# ESP32_breakout_v3.net
KiCad netlist of a schematic drawn in EAGLE
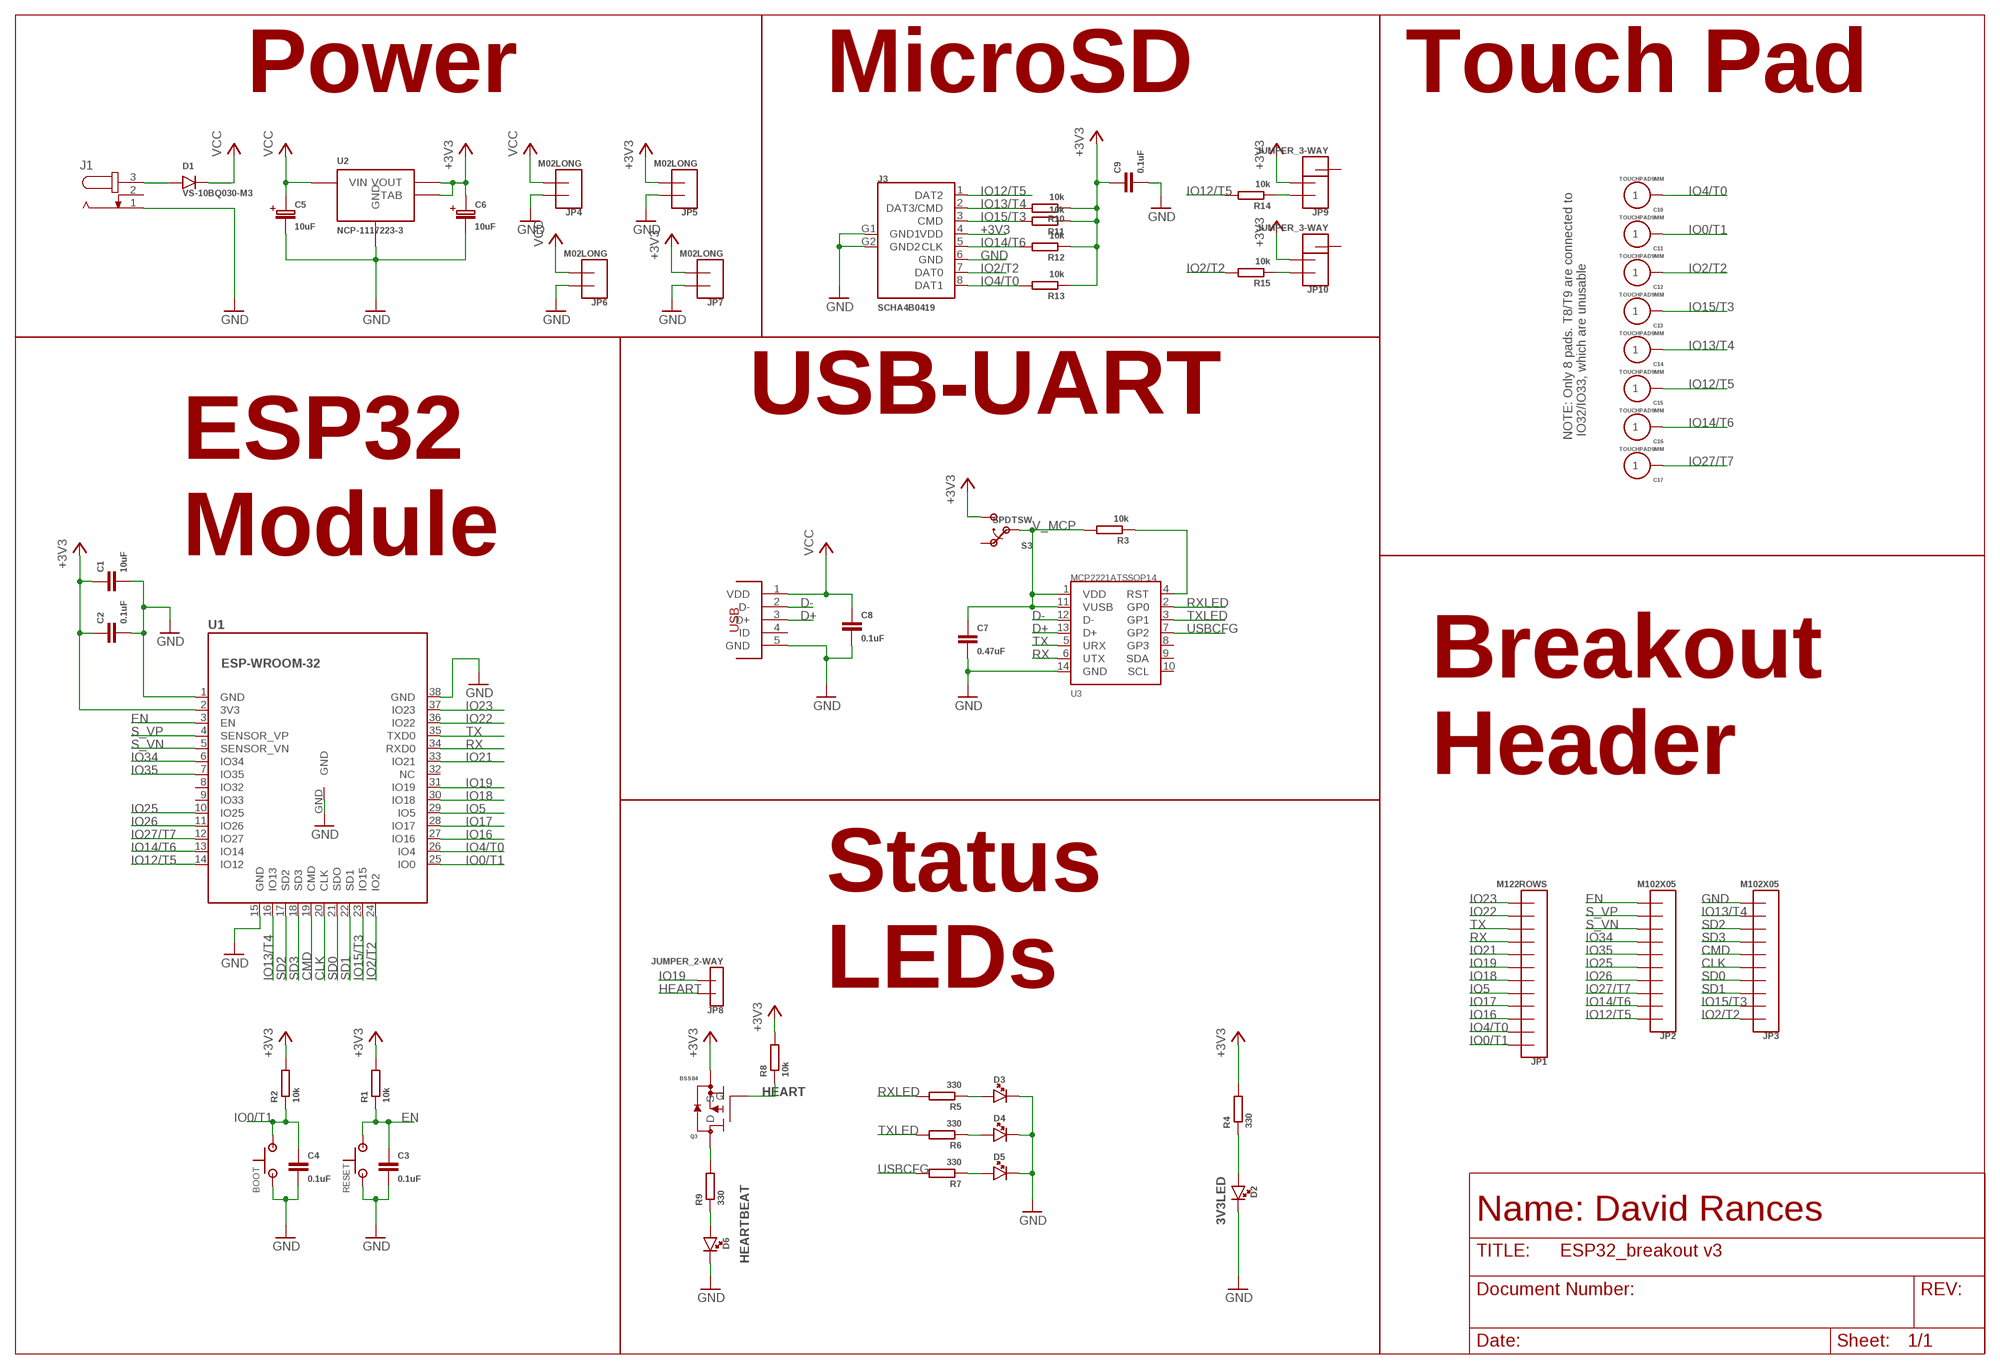
[diagram p0: schematic, sheet 1]

(export (version "E")
  (design (tool "Eeschema 10.0.6"))
  (components
    (comp (ref "BOOT")
      (value "PUSHBUTTONSKHMQME010")
      (footprint "eagle-import:SKHMQME010")
      (libsource (lib "eagle-import") (part "PUSHBUTTONSKHMQME010"))
    )
    (comp (ref "C1")
      (value "10uF")
      (footprint "eagle-import:CAP-0603")
      (libsource (lib "eagle-import") (part "CAP0603"))
    )
    (comp (ref "C2")
      (value "0.1uF")
      (footprint "eagle-import:CAP-0603")
      (libsource (lib "eagle-import") (part "CAP0603"))
    )
    (comp (ref "C3")
      (value "0.1uF")
      (footprint "eagle-import:CAP-0603")
      (libsource (lib "eagle-import") (part "CAP0603"))
    )
    (comp (ref "C4")
      (value "0.1uF")
      (footprint "eagle-import:CAP-0603")
      (libsource (lib "eagle-import") (part "CAP0603"))
    )
    (comp (ref "C5")
      (value "10uF")
      (footprint "eagle-import:B-3528")
      (libsource (lib "eagle-import") (part "CAP-POLARCASEB-3528"))
    )
    (comp (ref "C6")
      (value "10uF")
      (footprint "eagle-import:B-3528")
      (libsource (lib "eagle-import") (part "CAP-POLARCASEB-3528"))
    )
    (comp (ref "C7")
      (value "0.47uF")
      (footprint "eagle-import:CAP-0603")
      (libsource (lib "eagle-import") (part "CAP0603"))
    )
    (comp (ref "C8")
      (value "0.1uF")
      (footprint "eagle-import:CAP-0603")
      (libsource (lib "eagle-import") (part "CAP0603"))
    )
    (comp (ref "C9")
      (value "0.1uF")
      (footprint "eagle-import:CAP-0603")
      (libsource (lib "eagle-import") (part "CAP0603"))
    )
    (comp (ref "C10")
      (value "TOUCHPAD9MM")
      (footprint "eagle-import:TOUCH-9MMX9MM")
      (libsource (lib "eagle-import") (part "TOUCHPAD9MM"))
    )
    (comp (ref "C11")
      (value "TOUCHPAD9MM")
      (footprint "eagle-import:TOUCH-9MMX9MM")
      (libsource (lib "eagle-import") (part "TOUCHPAD9MM"))
    )
    (comp (ref "C12")
      (value "TOUCHPAD9MM")
      (footprint "eagle-import:TOUCH-9MMX9MM")
      (libsource (lib "eagle-import") (part "TOUCHPAD9MM"))
    )
    (comp (ref "C13")
      (value "TOUCHPAD9MM")
      (footprint "eagle-import:TOUCH-9MMX9MM")
      (libsource (lib "eagle-import") (part "TOUCHPAD9MM"))
    )
    (comp (ref "C14")
      (value "TOUCHPAD9MM")
      (footprint "eagle-import:TOUCH-9MMX9MM")
      (libsource (lib "eagle-import") (part "TOUCHPAD9MM"))
    )
    (comp (ref "C15")
      (value "TOUCHPAD9MM")
      (footprint "eagle-import:TOUCH-9MMX9MM")
      (libsource (lib "eagle-import") (part "TOUCHPAD9MM"))
    )
    (comp (ref "C16")
      (value "TOUCHPAD9MM")
      (footprint "eagle-import:TOUCH-9MMX9MM")
      (libsource (lib "eagle-import") (part "TOUCHPAD9MM"))
    )
    (comp (ref "C17")
      (value "TOUCHPAD9MM")
      (footprint "eagle-import:TOUCH-9MMX9MM")
      (libsource (lib "eagle-import") (part "TOUCHPAD9MM"))
    )
    (comp (ref "D1")
      (value "VS-10BQ030-M3")
      (footprint "eagle-import:DO-214AA")
      (libsource (lib "eagle-import") (part "VS-10BQ030-M3"))
    )
    (comp (ref "D2")
      (value "LED1206")
      (footprint "eagle-import:LED-1206")
      (libsource (lib "eagle-import") (part "LED1206"))
    )
    (comp (ref "D3")
      (value "LED1206")
      (footprint "eagle-import:LED-1206")
      (libsource (lib "eagle-import") (part "LED1206"))
    )
    (comp (ref "D4")
      (value "LED1206")
      (footprint "eagle-import:LED-1206")
      (libsource (lib "eagle-import") (part "LED1206"))
    )
    (comp (ref "D5")
      (value "LED1206")
      (footprint "eagle-import:LED-1206")
      (libsource (lib "eagle-import") (part "LED1206"))
    )
    (comp (ref "D6")
      (value "LED1206")
      (footprint "eagle-import:LED-1206")
      (libsource (lib "eagle-import") (part "LED1206"))
    )
    (comp (ref "J1")
      (value "JACK-PLUG0")
      (footprint "eagle-import:SPC4077")
      (libsource (lib "eagle-import") (part "JACK-PLUG0"))
    )
    (comp (ref "J3")
      (value "SCHA4B0419")
      (footprint "eagle-import:MICROSD_SCHA4B0419")
      (libsource (lib "eagle-import") (part "SCHA4B0419"))
    )
    (comp (ref "JP1")
      (value "M122ROWS")
      (footprint "eagle-import:2X06")
      (libsource (lib "eagle-import") (part "M122ROWS"))
    )
    (comp (ref "JP2")
      (value "M102X05")
      (footprint "eagle-import:2X05")
      (libsource (lib "eagle-import") (part "M102X05"))
    )
    (comp (ref "JP3")
      (value "M102X05")
      (footprint "eagle-import:2X05")
      (libsource (lib "eagle-import") (part "M102X05"))
    )
    (comp (ref "JP4")
      (value "M02LONG")
      (footprint "eagle-import:1X02-LONG")
      (libsource (lib "eagle-import") (part "M02LONG"))
    )
    (comp (ref "JP5")
      (value "M02LONG")
      (footprint "eagle-import:1X02-LONG")
      (libsource (lib "eagle-import") (part "M02LONG"))
    )
    (comp (ref "JP6")
      (value "M02LONG")
      (footprint "eagle-import:1X02-LONG")
      (libsource (lib "eagle-import") (part "M02LONG"))
    )
    (comp (ref "JP7")
      (value "M02LONG")
      (footprint "eagle-import:1X02-LONG")
      (libsource (lib "eagle-import") (part "M02LONG"))
    )
    (comp (ref "JP8")
      (value "JUMPER_2-WAY")
      (footprint "eagle-import:1X02")
      (libsource (lib "eagle-import") (part "JUMPER_2-WAY"))
    )
    (comp (ref "JP9")
      (value "JUMPER_3-WAY")
      (footprint "eagle-import:1X03")
      (libsource (lib "eagle-import") (part "JUMPER_3-WAY"))
    )
    (comp (ref "JP10")
      (value "JUMPER_3-WAY")
      (footprint "eagle-import:1X03")
      (libsource (lib "eagle-import") (part "JUMPER_3-WAY"))
    )
    (comp (ref "Q3")
      (value "BSS84")
      (footprint "eagle-import:SOT-23-3")
      (libsource (lib "eagle-import") (part "BSS84"))
    )
    (comp (ref "R1")
      (value "10k")
      (footprint "eagle-import:RES-0603")
      (libsource (lib "eagle-import") (part "RESISTOR0603"))
    )
    (comp (ref "R2")
      (value "10k")
      (footprint "eagle-import:RES-0603")
      (libsource (lib "eagle-import") (part "RESISTOR0603"))
    )
    (comp (ref "R3")
      (value "10k")
      (footprint "eagle-import:RES-0603")
      (libsource (lib "eagle-import") (part "RESISTOR0603"))
    )
    (comp (ref "R4")
      (value "330")
      (footprint "eagle-import:RES-0603")
      (libsource (lib "eagle-import") (part "RESISTOR0603"))
    )
    (comp (ref "R5")
      (value "330")
      (footprint "eagle-import:RES-0603")
      (libsource (lib "eagle-import") (part "RESISTOR0603"))
    )
    (comp (ref "R6")
      (value "330")
      (footprint "eagle-import:RES-0603")
      (libsource (lib "eagle-import") (part "RESISTOR0603"))
    )
    (comp (ref "R7")
      (value "330")
      (footprint "eagle-import:RES-0603")
      (libsource (lib "eagle-import") (part "RESISTOR0603"))
    )
    (comp (ref "R8")
      (value "10k")
      (footprint "eagle-import:RES-0603")
      (libsource (lib "eagle-import") (part "RESISTOR0603"))
    )
    (comp (ref "R9")
      (value "330")
      (footprint "eagle-import:RES-0603")
      (libsource (lib "eagle-import") (part "RESISTOR0603"))
    )
    (comp (ref "R10")
      (value "10k")
      (footprint "eagle-import:RES-0603")
      (libsource (lib "eagle-import") (part "RESISTOR0603"))
    )
    (comp (ref "R11")
      (value "10k")
      (footprint "eagle-import:RES-0603")
      (libsource (lib "eagle-import") (part "RESISTOR0603"))
    )
    (comp (ref "R12")
      (value "10k")
      (footprint "eagle-import:RES-0603")
      (libsource (lib "eagle-import") (part "RESISTOR0603"))
    )
    (comp (ref "R13")
      (value "10k")
      (footprint "eagle-import:RES-0603")
      (libsource (lib "eagle-import") (part "RESISTOR0603"))
    )
    (comp (ref "R14")
      (value "10k")
      (footprint "eagle-import:RES-0603")
      (libsource (lib "eagle-import") (part "RESISTOR0603"))
    )
    (comp (ref "R15")
      (value "10k")
      (footprint "eagle-import:RES-0603")
      (libsource (lib "eagle-import") (part "RESISTOR0603"))
    )
    (comp (ref "RESET")
      (value "PUSHBUTTONSKHMQME010")
      (footprint "eagle-import:SKHMQME010")
      (libsource (lib "eagle-import") (part "PUSHBUTTONSKHMQME010"))
    )
    (comp (ref "S3")
      (value "SPDTSW")
      (footprint "eagle-import:SPDT_TH")
      (libsource (lib "eagle-import") (part "SPDTSW"))
    )
    (comp (ref "U$4")
      (value "MOLEX_USBMICRO")
      (footprint "eagle-import:MOLEX_47346-001")
      (libsource (lib "eagle-import") (part "MOLEX_USBMICRO"))
    )
    (comp (ref "U1")
      (value "ESP-WROOM-32")
      (footprint "eagle-import:ESP-WROOM-32")
      (libsource (lib "eagle-import") (part "ESP-WROOM-32"))
    )
    (comp (ref "U2")
      (value "NCP-1117223-3")
      (footprint "eagle-import:SOT-223-3")
      (libsource (lib "eagle-import") (part "NCP-1117223-3"))
    )
    (comp (ref "U3")
      (value "MCP2221ATSSOP14")
      (footprint "eagle-import:TSSOP-14")
      (libsource (lib "eagle-import") (part "MCP2221ATSSOP14"))
    )
  )
  (nets
    (net (code "1") (name "+3V3") (class "Default")
      (node (ref "C1") (pin "1") (pinfunction "1_1") (pintype "passive"))
      (node (ref "C2") (pin "1") (pinfunction "1_1") (pintype "passive"))
      (node (ref "C6") (pin "P") (pinfunction "P_P") (pintype "passive"))
      (node (ref "C9") (pin "1") (pinfunction "1_1") (pintype "passive"))
      (node (ref "J3") (pin "4") (pinfunction "VDD_4") (pintype "bidirectional"))
      (node (ref "JP10") (pin "2") (pinfunction "2_2") (pintype "bidirectional"))
      (node (ref "JP5") (pin "2") (pinfunction "2_2") (pintype "bidirectional"))
      (node (ref "JP7") (pin "2") (pinfunction "2_2") (pintype "bidirectional"))
      (node (ref "JP9") (pin "2") (pinfunction "2_2") (pintype "bidirectional"))
      (node (ref "Q3") (pin "S") (pinfunction "S_S") (pintype "bidirectional"))
      (node (ref "R1") (pin "2") (pinfunction "2_2") (pintype "passive"))
      (node (ref "R10") (pin "1") (pinfunction "1_1") (pintype "passive"))
      (node (ref "R11") (pin "1") (pinfunction "1_1") (pintype "passive"))
      (node (ref "R12") (pin "1") (pinfunction "1_1") (pintype "passive"))
      (node (ref "R13") (pin "1") (pinfunction "1_1") (pintype "passive"))
      (node (ref "R2") (pin "2") (pinfunction "2_2") (pintype "passive"))
      (node (ref "R4") (pin "2") (pinfunction "2_2") (pintype "passive"))
      (node (ref "R8") (pin "2") (pinfunction "2_2") (pintype "passive"))
      (node (ref "S3") (pin "3") (pinfunction "2_3") (pintype "bidirectional"))
      (node (ref "U1") (pin "2") (pinfunction "3V3_2") (pintype "bidirectional"))
      (node (ref "U2") (pin "2") (pinfunction "VOUT_2") (pintype "power_in"))
      (node (ref "U2") (pin "PAD") (pinfunction "TAB_PAD") (pintype "power_in"))
    )
    (net (code "2") (name "/CLK") (class "Default")
      (node (ref "JP3") (pin "5") (pinfunction "5_5") (pintype "bidirectional"))
      (node (ref "U1") (pin "20") (pinfunction "CLK_20") (pintype "bidirectional"))
    )
    (net (code "3") (name "/CMD") (class "Default")
      (node (ref "JP3") (pin "6") (pinfunction "6_6") (pintype "bidirectional"))
      (node (ref "U1") (pin "19") (pinfunction "CMD_19") (pintype "bidirectional"))
    )
    (net (code "4") (name "/D+") (class "Default")
      (node (ref "U$4") (pin "3") (pinfunction "D+_3") (pintype "bidirectional"))
      (node (ref "U3") (pin "13") (pinfunction "D+_13") (pintype "bidirectional"))
    )
    (net (code "5") (name "/D-") (class "Default")
      (node (ref "U$4") (pin "2") (pinfunction "D-_2") (pintype "bidirectional"))
      (node (ref "U3") (pin "12") (pinfunction "D-_12") (pintype "bidirectional"))
    )
    (net (code "6") (name "/EN") (class "Default")
      (node (ref "C3") (pin "1") (pinfunction "1_1") (pintype "passive"))
      (node (ref "JP2") (pin "10") (pinfunction "10_10") (pintype "bidirectional"))
      (node (ref "R1") (pin "1") (pinfunction "1_1") (pintype "passive"))
      (node (ref "RESET") (pin "3") (pinfunction "2_3") (pintype "bidirectional"))
      (node (ref "RESET") (pin "4") (pinfunction "2_4") (pintype "bidirectional"))
      (node (ref "U1") (pin "3") (pinfunction "EN_3") (pintype "bidirectional"))
    )
    (net (code "7") (name "/HEART") (class "Default")
      (node (ref "JP8") (pin "1") (pinfunction "1_1") (pintype "bidirectional"))
      (node (ref "Q3") (pin "G") (pinfunction "G_G") (pintype "bidirectional"))
      (node (ref "R8") (pin "1") (pinfunction "1_1") (pintype "passive"))
    )
    (net (code "8") (name "/IO0{slash}T1") (class "Default")
      (node (ref "BOOT") (pin "3") (pinfunction "2_3") (pintype "bidirectional"))
      (node (ref "BOOT") (pin "4") (pinfunction "2_4") (pintype "bidirectional"))
      (node (ref "C11") (pin "P$1") (pinfunction "1_P$1") (pintype "bidirectional"))
      (node (ref "C4") (pin "1") (pinfunction "1_1") (pintype "passive"))
      (node (ref "JP1") (pin "1") (pinfunction "1_1") (pintype "bidirectional"))
      (node (ref "R2") (pin "1") (pinfunction "1_1") (pintype "passive"))
      (node (ref "U1") (pin "25") (pinfunction "IO0_25") (pintype "bidirectional"))
    )
    (net (code "9") (name "/IO2{slash}T2") (class "Default")
      (node (ref "C12") (pin "P$1") (pinfunction "1_P$1") (pintype "bidirectional"))
      (node (ref "J3") (pin "7") (pinfunction "DAT0_7") (pintype "bidirectional"))
      (node (ref "JP3") (pin "1") (pinfunction "1_1") (pintype "bidirectional"))
      (node (ref "R15") (pin "2") (pinfunction "2_2") (pintype "passive"))
      (node (ref "U1") (pin "24") (pinfunction "IO2_24") (pintype "bidirectional"))
    )
    (net (code "10") (name "/IO4{slash}T0") (class "Default")
      (node (ref "C10") (pin "P$1") (pinfunction "1_P$1") (pintype "bidirectional"))
      (node (ref "J3") (pin "8") (pinfunction "DAT1_8") (pintype "bidirectional"))
      (node (ref "JP1") (pin "2") (pinfunction "2_2") (pintype "bidirectional"))
      (node (ref "R13") (pin "2") (pinfunction "2_2") (pintype "passive"))
      (node (ref "U1") (pin "26") (pinfunction "IO4_26") (pintype "bidirectional"))
    )
    (net (code "11") (name "/IO5") (class "Default")
      (node (ref "JP1") (pin "5") (pinfunction "5_5") (pintype "bidirectional"))
      (node (ref "U1") (pin "29") (pinfunction "IO5_29") (pintype "bidirectional"))
    )
    (net (code "12") (name "/IO12{slash}T5") (class "Default")
      (node (ref "C15") (pin "P$1") (pinfunction "1_P$1") (pintype "bidirectional"))
      (node (ref "J3") (pin "1") (pinfunction "DAT2_1") (pintype "bidirectional"))
      (node (ref "JP2") (pin "1") (pinfunction "1_1") (pintype "bidirectional"))
      (node (ref "R14") (pin "2") (pinfunction "2_2") (pintype "passive"))
      (node (ref "U1") (pin "14") (pinfunction "IO12_14") (pintype "bidirectional"))
    )
    (net (code "13") (name "/IO13{slash}T4") (class "Default")
      (node (ref "C14") (pin "P$1") (pinfunction "1_P$1") (pintype "bidirectional"))
      (node (ref "J3") (pin "2") (pinfunction "DAT3/CMD_2") (pintype "bidirectional"))
      (node (ref "JP3") (pin "9") (pinfunction "9_9") (pintype "bidirectional"))
      (node (ref "R10") (pin "2") (pinfunction "2_2") (pintype "passive"))
      (node (ref "U1") (pin "16") (pinfunction "IO13_16") (pintype "bidirectional"))
    )
    (net (code "14") (name "/IO14{slash}T6") (class "Default")
      (node (ref "C16") (pin "P$1") (pinfunction "1_P$1") (pintype "bidirectional"))
      (node (ref "J3") (pin "5") (pinfunction "CLK_5") (pintype "bidirectional"))
      (node (ref "JP2") (pin "2") (pinfunction "2_2") (pintype "bidirectional"))
      (node (ref "R12") (pin "2") (pinfunction "2_2") (pintype "passive"))
      (node (ref "U1") (pin "13") (pinfunction "IO14_13") (pintype "bidirectional"))
    )
    (net (code "15") (name "/IO15{slash}T3") (class "Default")
      (node (ref "C13") (pin "P$1") (pinfunction "1_P$1") (pintype "bidirectional"))
      (node (ref "J3") (pin "3") (pinfunction "CMD_3") (pintype "bidirectional"))
      (node (ref "JP3") (pin "2") (pinfunction "2_2") (pintype "bidirectional"))
      (node (ref "R11") (pin "2") (pinfunction "2_2") (pintype "passive"))
      (node (ref "U1") (pin "23") (pinfunction "IO15_23") (pintype "bidirectional"))
    )
    (net (code "16") (name "/IO16") (class "Default")
      (node (ref "JP1") (pin "3") (pinfunction "3_3") (pintype "bidirectional"))
      (node (ref "U1") (pin "27") (pinfunction "IO16_27") (pintype "bidirectional"))
    )
    (net (code "17") (name "/IO17") (class "Default")
      (node (ref "JP1") (pin "4") (pinfunction "4_4") (pintype "bidirectional"))
      (node (ref "U1") (pin "28") (pinfunction "IO17_28") (pintype "bidirectional"))
    )
    (net (code "18") (name "/IO18") (class "Default")
      (node (ref "JP1") (pin "6") (pinfunction "6_6") (pintype "bidirectional"))
      (node (ref "U1") (pin "30") (pinfunction "IO18_30") (pintype "bidirectional"))
    )
    (net (code "19") (name "/IO19") (class "Default")
      (node (ref "JP1") (pin "7") (pinfunction "7_7") (pintype "bidirectional"))
      (node (ref "JP8") (pin "2") (pinfunction "2_2") (pintype "bidirectional"))
      (node (ref "U1") (pin "31") (pinfunction "IO19_31") (pintype "bidirectional"))
    )
    (net (code "20") (name "/IO21") (class "Default")
      (node (ref "JP1") (pin "8") (pinfunction "8_8") (pintype "bidirectional"))
      (node (ref "U1") (pin "33") (pinfunction "IO21_33") (pintype "bidirectional"))
    )
    (net (code "21") (name "/IO22") (class "Default")
      (node (ref "JP1") (pin "11") (pinfunction "11_11") (pintype "bidirectional"))
      (node (ref "U1") (pin "36") (pinfunction "IO22_36") (pintype "bidirectional"))
    )
    (net (code "22") (name "/IO23") (class "Default")
      (node (ref "JP1") (pin "12") (pinfunction "12_12") (pintype "bidirectional"))
      (node (ref "U1") (pin "37") (pinfunction "IO23_37") (pintype "bidirectional"))
    )
    (net (code "23") (name "/IO25") (class "Default")
      (node (ref "JP2") (pin "5") (pinfunction "5_5") (pintype "bidirectional"))
      (node (ref "U1") (pin "10") (pinfunction "IO25_10") (pintype "bidirectional"))
    )
    (net (code "24") (name "/IO26") (class "Default")
      (node (ref "JP2") (pin "4") (pinfunction "4_4") (pintype "bidirectional"))
      (node (ref "U1") (pin "11") (pinfunction "IO26_11") (pintype "bidirectional"))
    )
    (net (code "25") (name "/IO27{slash}T7") (class "Default")
      (node (ref "C17") (pin "P$1") (pinfunction "1_P$1") (pintype "bidirectional"))
      (node (ref "JP2") (pin "3") (pinfunction "3_3") (pintype "bidirectional"))
      (node (ref "U1") (pin "12") (pinfunction "IO27_12") (pintype "bidirectional"))
    )
    (net (code "26") (name "/IO34") (class "Default")
      (node (ref "JP2") (pin "7") (pinfunction "7_7") (pintype "bidirectional"))
      (node (ref "U1") (pin "6") (pinfunction "IO34_6") (pintype "bidirectional"))
    )
    (net (code "27") (name "/IO35") (class "Default")
      (node (ref "JP2") (pin "6") (pinfunction "6_6") (pintype "bidirectional"))
      (node (ref "U1") (pin "7") (pinfunction "IO35_7") (pintype "bidirectional"))
    )
    (net (code "28") (name "/RX") (class "Default")
      (node (ref "JP1") (pin "9") (pinfunction "9_9") (pintype "bidirectional"))
      (node (ref "U1") (pin "34") (pinfunction "RXD0_34") (pintype "bidirectional"))
      (node (ref "U3") (pin "6") (pinfunction "UTX_6") (pintype "bidirectional"))
    )
    (net (code "29") (name "/RXLED") (class "Default")
      (node (ref "R5") (pin "2") (pinfunction "2_2") (pintype "passive"))
      (node (ref "U3") (pin "2") (pinfunction "GP0_2") (pintype "bidirectional"))
    )
    (net (code "30") (name "/SD0") (class "Default")
      (node (ref "JP3") (pin "4") (pinfunction "4_4") (pintype "bidirectional"))
      (node (ref "U1") (pin "21") (pinfunction "SDO_21") (pintype "bidirectional"))
    )
    (net (code "31") (name "/SD1") (class "Default")
      (node (ref "JP3") (pin "3") (pinfunction "3_3") (pintype "bidirectional"))
      (node (ref "U1") (pin "22") (pinfunction "SD1_22") (pintype "bidirectional"))
    )
    (net (code "32") (name "/SD2") (class "Default")
      (node (ref "JP3") (pin "8") (pinfunction "8_8") (pintype "bidirectional"))
      (node (ref "U1") (pin "17") (pinfunction "SD2_17") (pintype "bidirectional"))
    )
    (net (code "33") (name "/SD3") (class "Default")
      (node (ref "JP3") (pin "7") (pinfunction "7_7") (pintype "bidirectional"))
      (node (ref "U1") (pin "18") (pinfunction "SD3_18") (pintype "bidirectional"))
    )
    (net (code "34") (name "/S_VN") (class "Default")
      (node (ref "JP2") (pin "8") (pinfunction "8_8") (pintype "bidirectional"))
      (node (ref "U1") (pin "5") (pinfunction "SENSOR_VN_5") (pintype "bidirectional"))
    )
    (net (code "35") (name "/S_VP") (class "Default")
      (node (ref "JP2") (pin "9") (pinfunction "9_9") (pintype "bidirectional"))
      (node (ref "U1") (pin "4") (pinfunction "SENSOR_VP_4") (pintype "bidirectional"))
    )
    (net (code "36") (name "/TX") (class "Default")
      (node (ref "JP1") (pin "10") (pinfunction "10_10") (pintype "bidirectional"))
      (node (ref "U1") (pin "35") (pinfunction "TXD0_35") (pintype "bidirectional"))
      (node (ref "U3") (pin "5") (pinfunction "URX_5") (pintype "bidirectional"))
    )
    (net (code "37") (name "/TXLED") (class "Default")
      (node (ref "R6") (pin "2") (pinfunction "2_2") (pintype "passive"))
      (node (ref "U3") (pin "3") (pinfunction "GP1_3") (pintype "bidirectional"))
    )
    (net (code "38") (name "/USBCFG") (class "Default")
      (node (ref "R7") (pin "2") (pinfunction "2_2") (pintype "passive"))
      (node (ref "U3") (pin "7") (pinfunction "GP2_7") (pintype "bidirectional"))
    )
    (net (code "39") (name "/V_MCP") (class "Default")
      (node (ref "C7") (pin "1") (pinfunction "1_1") (pintype "passive"))
      (node (ref "R3") (pin "2") (pinfunction "2_2") (pintype "passive"))
      (node (ref "S3") (pin "2") (pinfunction "OUT_2") (pintype "bidirectional"))
      (node (ref "U3") (pin "1") (pinfunction "VDD_1") (pintype "bidirectional"))
      (node (ref "U3") (pin "11") (pinfunction "VUSB_11") (pintype "bidirectional"))
    )
    (net (code "40") (name "GND") (class "Default")
      (node (ref "BOOT") (pin "1") (pinfunction "1_1") (pintype "bidirectional"))
      (node (ref "BOOT") (pin "2") (pinfunction "1_2") (pintype "bidirectional"))
      (node (ref "C1") (pin "2") (pinfunction "2_2") (pintype "passive"))
      (node (ref "C2") (pin "2") (pinfunction "2_2") (pintype "passive"))
      (node (ref "C3") (pin "2") (pinfunction "2_2") (pintype "passive"))
      (node (ref "C4") (pin "2") (pinfunction "2_2") (pintype "passive"))
      (node (ref "C5") (pin "N") (pinfunction "N_N") (pintype "passive"))
      (node (ref "C6") (pin "N") (pinfunction "N_N") (pintype "passive"))
      (node (ref "C7") (pin "2") (pinfunction "2_2") (pintype "passive"))
      (node (ref "C8") (pin "2") (pinfunction "2_2") (pintype "passive"))
      (node (ref "C9") (pin "2") (pinfunction "2_2") (pintype "passive"))
      (node (ref "D2") (pin "C") (pinfunction "C_C") (pintype "bidirectional"))
      (node (ref "D3") (pin "C") (pinfunction "C_C") (pintype "bidirectional"))
      (node (ref "D4") (pin "C") (pinfunction "C_C") (pintype "bidirectional"))
      (node (ref "D5") (pin "C") (pinfunction "C_C") (pintype "bidirectional"))
      (node (ref "D6") (pin "C") (pinfunction "C_C") (pintype "bidirectional"))
      (node (ref "J1") (pin "1") (pinfunction "1_1") (pintype "passive"))
      (node (ref "J3") (pin "6") (pinfunction "GND_6") (pintype "bidirectional"))
      (node (ref "J3") (pin "G1") (pinfunction "GND1_G1") (pintype "bidirectional"))
      (node (ref "J3") (pin "G2") (pinfunction "GND2_G2") (pintype "bidirectional"))
      (node (ref "JP3") (pin "10") (pinfunction "10_10") (pintype "bidirectional"))
      (node (ref "JP4") (pin "1") (pinfunction "1_1") (pintype "bidirectional"))
      (node (ref "JP5") (pin "1") (pinfunction "1_1") (pintype "bidirectional"))
      (node (ref "JP6") (pin "1") (pinfunction "1_1") (pintype "bidirectional"))
      (node (ref "JP7") (pin "1") (pinfunction "1_1") (pintype "bidirectional"))
      (node (ref "RESET") (pin "1") (pinfunction "1_1") (pintype "bidirectional"))
      (node (ref "RESET") (pin "2") (pinfunction "1_2") (pintype "bidirectional"))
      (node (ref "U$4") (pin "5") (pinfunction "GND_5") (pintype "bidirectional"))
      (node (ref "U1") (pin "1") (pinfunction "GND_1") (pintype "bidirectional"))
      (node (ref "U1") (pin "15") (pinfunction "GND_15") (pintype "bidirectional"))
      (node (ref "U1") (pin "38") (pinfunction "GND_38") (pintype "bidirectional"))
      (node (ref "U1") (pin "GND") (pinfunction "GND_GND") (pintype "bidirectional"))
      (node (ref "U2") (pin "1") (pinfunction "GND_1") (pintype "power_in"))
      (node (ref "U3") (pin "14") (pinfunction "GND_14") (pintype "bidirectional"))
    )
    (net (code "41") (name "Net-(D1-PadA)") (class "Default")
      (node (ref "D1") (pin "A") (pinfunction "A_A") (pintype "bidirectional"))
      (node (ref "J1") (pin "3") (pinfunction "3_3") (pintype "passive"))
    )
    (net (code "42") (name "Net-(D2-PadA)") (class "Default")
      (node (ref "D2") (pin "A") (pinfunction "A_A") (pintype "bidirectional"))
      (node (ref "R4") (pin "1") (pinfunction "1_1") (pintype "passive"))
    )
    (net (code "43") (name "Net-(D3-PadA)") (class "Default")
      (node (ref "D3") (pin "A") (pinfunction "A_A") (pintype "bidirectional"))
      (node (ref "R5") (pin "1") (pinfunction "1_1") (pintype "passive"))
    )
    (net (code "44") (name "Net-(D4-PadA)") (class "Default")
      (node (ref "D4") (pin "A") (pinfunction "A_A") (pintype "bidirectional"))
      (node (ref "R6") (pin "1") (pinfunction "1_1") (pintype "passive"))
    )
    (net (code "45") (name "Net-(D5-PadA)") (class "Default")
      (node (ref "D5") (pin "A") (pinfunction "A_A") (pintype "bidirectional"))
      (node (ref "R7") (pin "1") (pinfunction "1_1") (pintype "passive"))
    )
    (net (code "46") (name "Net-(D6-PadA)") (class "Default")
      (node (ref "D6") (pin "A") (pinfunction "A_A") (pintype "bidirectional"))
      (node (ref "R9") (pin "1") (pinfunction "1_1") (pintype "passive"))
    )
    (net (code "47") (name "Net-(JP9-Pad1)") (class "Default")
      (node (ref "JP9") (pin "1") (pinfunction "1_1") (pintype "bidirectional"))
      (node (ref "R14") (pin "1") (pinfunction "1_1") (pintype "passive"))
    )
    (net (code "48") (name "Net-(JP10-Pad1)") (class "Default")
      (node (ref "JP10") (pin "1") (pinfunction "1_1") (pintype "bidirectional"))
      (node (ref "R15") (pin "1") (pinfunction "1_1") (pintype "passive"))
    )
    (net (code "49") (name "Net-(Q3-PadD)") (class "Default")
      (node (ref "Q3") (pin "D") (pinfunction "D_D") (pintype "bidirectional"))
      (node (ref "R9") (pin "2") (pinfunction "2_2") (pintype "passive"))
    )
    (net (code "50") (name "Net-(U3-RST)") (class "Default")
      (node (ref "R3") (pin "1") (pinfunction "1_1") (pintype "passive"))
      (node (ref "U3") (pin "4") (pinfunction "RST_4") (pintype "bidirectional"))
    )
    (net (code "51") (name "VCC") (class "Default")
      (node (ref "C5") (pin "P") (pinfunction "P_P") (pintype "passive"))
      (node (ref "C8") (pin "1") (pinfunction "1_1") (pintype "passive"))
      (node (ref "D1") (pin "C") (pinfunction "C_C") (pintype "bidirectional"))
      (node (ref "JP4") (pin "2") (pinfunction "2_2") (pintype "bidirectional"))
      (node (ref "JP6") (pin "2") (pinfunction "2_2") (pintype "bidirectional"))
      (node (ref "U$4") (pin "1") (pinfunction "VDD_1") (pintype "bidirectional"))
      (node (ref "U2") (pin "3") (pinfunction "VIN_3") (pintype "power_in"))
    )
    (net (code "52") (name "unconnected-(BOOT-3-Pad5)") (class "Default")
      (node (ref "BOOT") (pin "5") (pinfunction "3_5") (pintype "bidirectional"))
    )
    (net (code "53") (name "unconnected-(J1-Pad2)") (class "Default")
      (node (ref "J1") (pin "2") (pinfunction "2_2") (pintype "passive"))
    )
    (net (code "54") (name "unconnected-(JP9-Pad3)") (class "Default")
      (node (ref "JP9") (pin "3") (pinfunction "3_3") (pintype "bidirectional"))
    )
    (net (code "55") (name "unconnected-(JP10-Pad3)") (class "Default")
      (node (ref "JP10") (pin "3") (pinfunction "3_3") (pintype "bidirectional"))
    )
    (net (code "56") (name "unconnected-(RESET-3-Pad5)") (class "Default")
      (node (ref "RESET") (pin "5") (pinfunction "3_5") (pintype "bidirectional"))
    )
    (net (code "57") (name "unconnected-(S3-Pad1)") (class "Default")
      (node (ref "S3") (pin "1") (pinfunction "1_1") (pintype "bidirectional"))
    )
    (net (code "58") (name "unconnected-(U$4-ID-Pad4)") (class "Default")
      (node (ref "U$4") (pin "4") (pinfunction "ID_4") (pintype "bidirectional"))
    )
    (net (code "59") (name "unconnected-(U1-IO32-Pad8)") (class "Default")
      (node (ref "U1") (pin "8") (pinfunction "IO32_8") (pintype "bidirectional"))
    )
    (net (code "60") (name "unconnected-(U1-IO33-Pad9)") (class "Default")
      (node (ref "U1") (pin "9") (pinfunction "IO33_9") (pintype "bidirectional"))
    )
    (net (code "61") (name "unconnected-(U1-NC-Pad32)") (class "Default")
      (node (ref "U1") (pin "32") (pinfunction "NC_32") (pintype "bidirectional"))
    )
    (net (code "62") (name "unconnected-(U3-GP3-Pad8)") (class "Default")
      (node (ref "U3") (pin "8") (pinfunction "GP3_8") (pintype "bidirectional"))
    )
    (net (code "63") (name "unconnected-(U3-SCL-Pad10)") (class "Default")
      (node (ref "U3") (pin "10") (pinfunction "SCL_10") (pintype "bidirectional"))
    )
    (net (code "64") (name "unconnected-(U3-SDA-Pad9)") (class "Default")
      (node (ref "U3") (pin "9") (pinfunction "SDA_9") (pintype "bidirectional"))
    )
  )
)
